# pcb_v1_mod.net
KiCad netlist of a schematic drawn in EAGLE
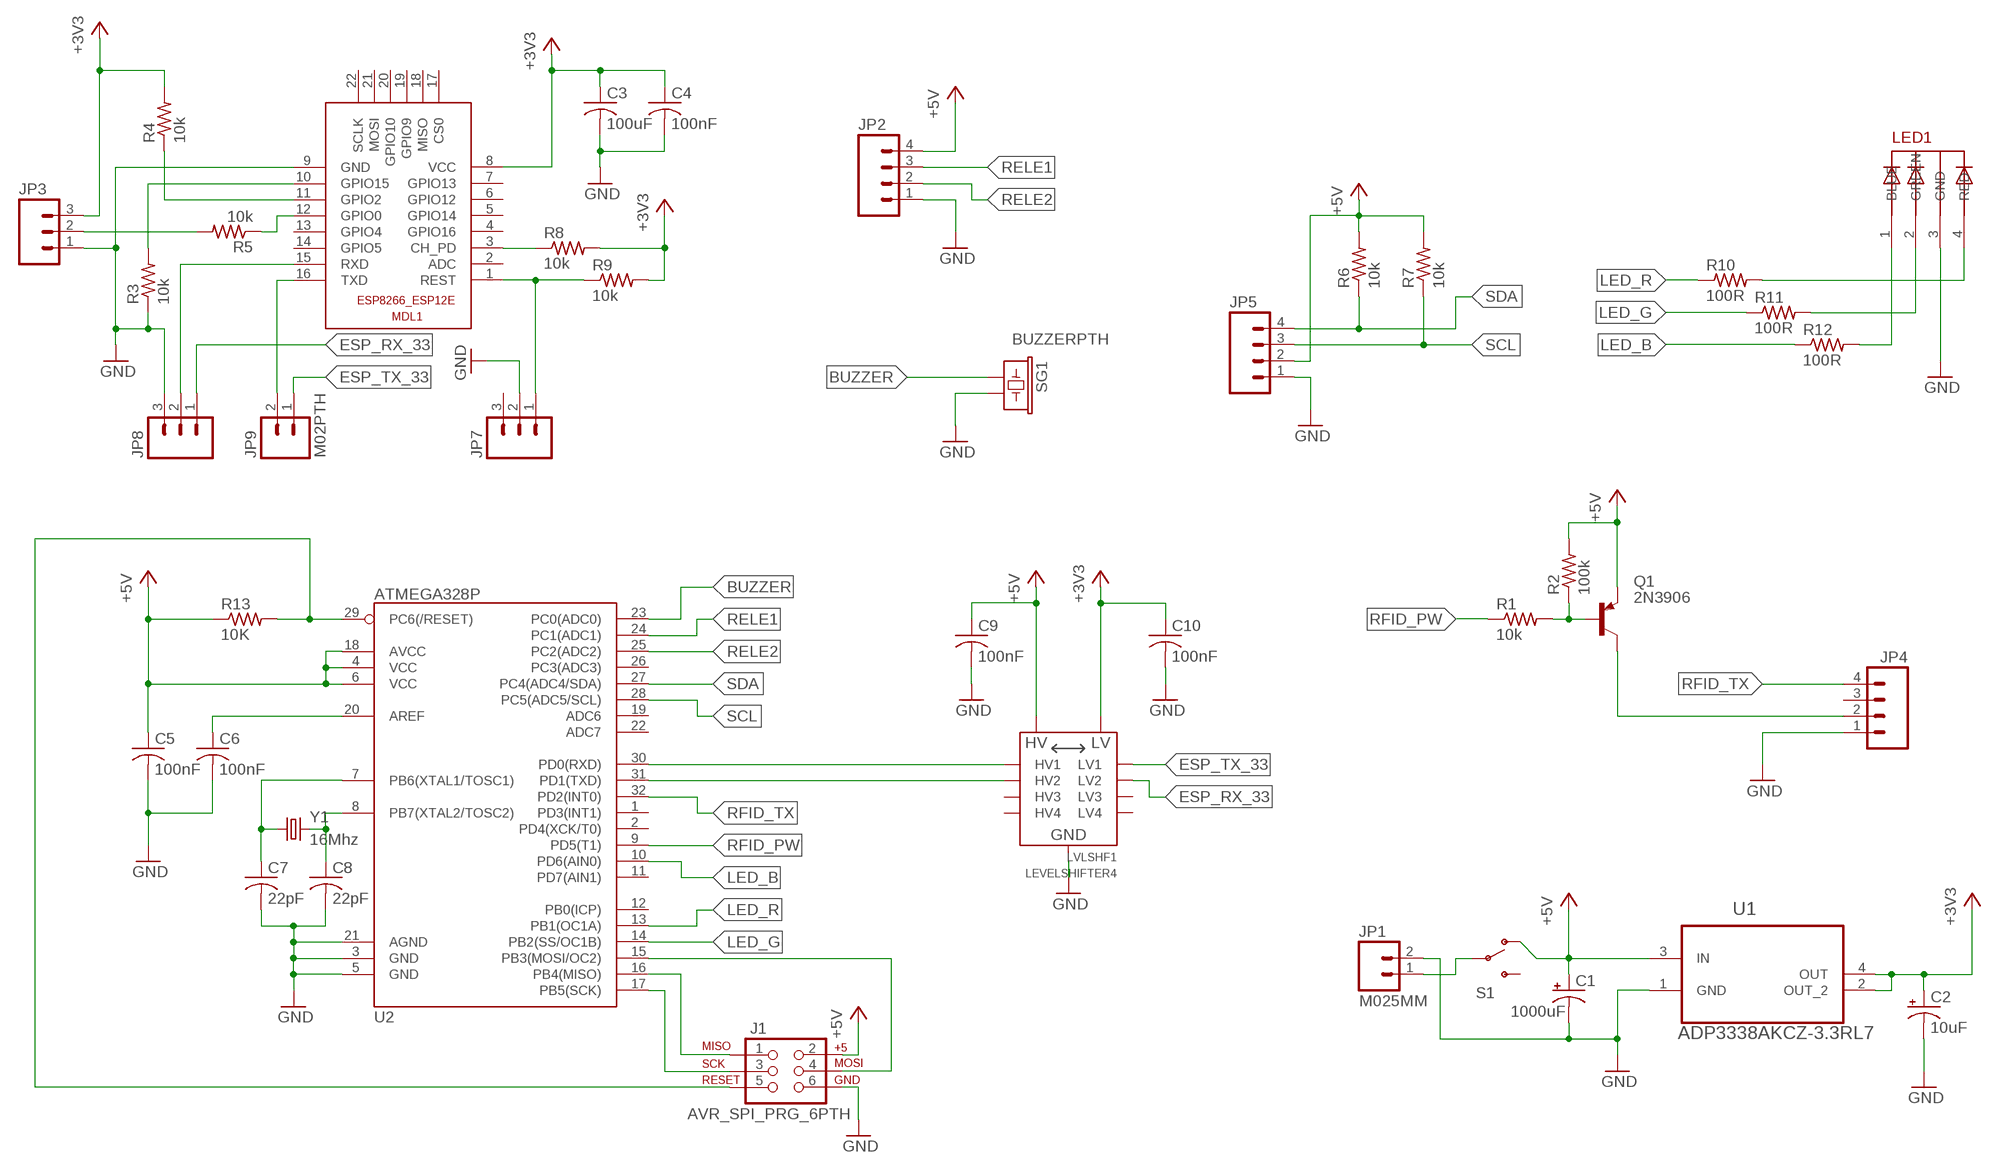
[diagram p0: schematic, sheet 1]

(export (version "E")
  (design (tool "Eeschema 10.0.6"))
  (components
    (comp (ref "C1")
      (value "1000uF")
      (footprint "eagle-import:E2,5-6")
      (libsource (lib "eagle-import") (part "CPOL-USE2.5-6"))
    )
    (comp (ref "C2")
      (value "10uF")
      (footprint "eagle-import:E2,5-6")
      (libsource (lib "eagle-import") (part "CPOL-USE2.5-6"))
    )
    (comp (ref "C3")
      (value "100uF")
      (footprint "eagle-import:C1206")
      (libsource (lib "eagle-import") (part "C-USC1206"))
    )
    (comp (ref "C4")
      (value "100nF")
      (footprint "eagle-import:C0805")
      (libsource (lib "eagle-import") (part "C-USC0805"))
    )
    (comp (ref "C5")
      (value "100nF")
      (footprint "eagle-import:C0805")
      (libsource (lib "eagle-import") (part "C-USC0805"))
    )
    (comp (ref "C6")
      (value "100nF")
      (footprint "eagle-import:C0805")
      (libsource (lib "eagle-import") (part "C-USC0805"))
    )
    (comp (ref "C7")
      (value "22pF")
      (footprint "eagle-import:C1206")
      (libsource (lib "eagle-import") (part "C-USC1206"))
    )
    (comp (ref "C8")
      (value "22pF")
      (footprint "eagle-import:C1206")
      (libsource (lib "eagle-import") (part "C-USC1206"))
    )
    (comp (ref "C9")
      (value "100nF")
      (footprint "eagle-import:C0805")
      (libsource (lib "eagle-import") (part "C-USC0805"))
    )
    (comp (ref "C10")
      (value "100nF")
      (footprint "eagle-import:C0805")
      (libsource (lib "eagle-import") (part "C-USC0805"))
    )
    (comp (ref "J1")
      (value "AVR_SPI_PRG_6PTH")
      (footprint "eagle-import:2X3")
      (libsource (lib "eagle-import") (part "AVR_SPI_PRG_6PTH"))
    )
    (comp (ref "JP1")
      (value "M025MM")
      (footprint "eagle-import:SCREWTERMINAL-5MM-2")
      (libsource (lib "eagle-import") (part "M025MM"))
    )
    (comp (ref "JP2")
      (value "M041X04_NO_SILK")
      (footprint "eagle-import:1X04_NO_SILK")
      (libsource (lib "eagle-import") (part "M041X04_NO_SILK"))
    )
    (comp (ref "JP3")
      (value "M03PTH")
      (footprint "eagle-import:1X03")
      (libsource (lib "eagle-import") (part "M03PTH"))
    )
    (comp (ref "JP4")
      (value "M041X04_NO_SILK")
      (footprint "eagle-import:1X04_NO_SILK")
      (libsource (lib "eagle-import") (part "M041X04_NO_SILK"))
    )
    (comp (ref "JP5")
      (value "M041X04_NO_SILK")
      (footprint "eagle-import:1X04_NO_SILK")
      (libsource (lib "eagle-import") (part "M041X04_NO_SILK"))
    )
    (comp (ref "JP7")
      (value "M03PTH")
      (footprint "eagle-import:1X03")
      (libsource (lib "eagle-import") (part "M03PTH"))
    )
    (comp (ref "JP8")
      (value "M03PTH")
      (footprint "eagle-import:1X03")
      (libsource (lib "eagle-import") (part "M03PTH"))
    )
    (comp (ref "JP9")
      (value "M02PTH")
      (footprint "eagle-import:1X02")
      (libsource (lib "eagle-import") (part "M02PTH"))
    )
    (comp (ref "LED1")
      (value "5MMRGBLED")
      (footprint "eagle-import:LED5MMRGB")
      (libsource (lib "eagle-import") (part "5MMRGBLED"))
    )
    (comp (ref "LVLSHF1")
      (value "LEVELSHIFTER4")
      (footprint "eagle-import:LEVELSHIFTER4")
      (libsource (lib "eagle-import") (part "LEVELSHIFTER4"))
    )
    (comp (ref "MDL1")
      (value "ESP8266-12EESP8266-ESP12E")
      (footprint "eagle-import:ESP8266-ESP12E")
      (libsource (lib "eagle-import") (part "ESP8266-12EESP8266-ESP12E"))
    )
    (comp (ref "Q1")
      (value "2N3906")
      (footprint "eagle-import:TO92")
      (libsource (lib "eagle-import") (part "2N3906"))
    )
    (comp (ref "R1")
      (value "10k")
      (footprint "eagle-import:R0805")
      (libsource (lib "eagle-import") (part "R-US_R0805"))
    )
    (comp (ref "R2")
      (value "100k")
      (footprint "eagle-import:R0805")
      (libsource (lib "eagle-import") (part "R-US_R0805"))
    )
    (comp (ref "R3")
      (value "10k")
      (footprint "eagle-import:R0805")
      (libsource (lib "eagle-import") (part "R-US_R0805"))
    )
    (comp (ref "R4")
      (value "10k")
      (footprint "eagle-import:R0805")
      (libsource (lib "eagle-import") (part "R-US_R0805"))
    )
    (comp (ref "R5")
      (value "10k")
      (footprint "eagle-import:R0805")
      (libsource (lib "eagle-import") (part "R-US_R0805"))
    )
    (comp (ref "R6")
      (value "10k")
      (footprint "eagle-import:R0805")
      (libsource (lib "eagle-import") (part "R-US_R0805"))
    )
    (comp (ref "R7")
      (value "10k")
      (footprint "eagle-import:R0805")
      (libsource (lib "eagle-import") (part "R-US_R0805"))
    )
    (comp (ref "R8")
      (value "10k")
      (footprint "eagle-import:R0805")
      (libsource (lib "eagle-import") (part "R-US_R0805"))
    )
    (comp (ref "R9")
      (value "10k")
      (footprint "eagle-import:R0805")
      (libsource (lib "eagle-import") (part "R-US_R0805"))
    )
    (comp (ref "R10")
      (value "100R")
      (footprint "eagle-import:R1206")
      (libsource (lib "eagle-import") (part "R-US_R1206"))
    )
    (comp (ref "R11")
      (value "100R")
      (footprint "eagle-import:R0805")
      (libsource (lib "eagle-import") (part "R-US_R0805"))
    )
    (comp (ref "R12")
      (value "100R")
      (footprint "eagle-import:R0805")
      (libsource (lib "eagle-import") (part "R-US_R0805"))
    )
    (comp (ref "R13")
      (value "10K")
      (footprint "eagle-import:R0805")
      (libsource (lib "eagle-import") (part "R-US_R0805"))
    )
    (comp (ref "S1")
      (value "SWITCH-SPDTPTH")
      (footprint "eagle-import:SWITCH-SPDT")
      (libsource (lib "eagle-import") (part "SWITCH-SPDTPTH"))
    )
    (comp (ref "SG1")
      (value "BUZZERPTH")
      (footprint "eagle-import:BUZZER-12MM")
      (libsource (lib "eagle-import") (part "BUZZERPTH"))
    )
    (comp (ref "U1")
      (value "ADP3338AKCZ-3.3RL7")
      (footprint "eagle-import:SOT230P700X180-4N")
      (libsource (lib "eagle-import") (part "ADP3338AKCZ-3.3RL7"))
    )
    (comp (ref "U2")
      (value "ATMEGA328P")
      (footprint "eagle-import:TQFP32-08")
      (libsource (lib "eagle-import") (part "ATMEGA328_SMT"))
    )
    (comp (ref "Y1")
      (value "16Mhz")
      (footprint "eagle-import:HC49US")
      (libsource (lib "eagle-import") (part "CRYSTALHC49US"))
    )
  )
  (nets
    (net (code "1") (name "+3V3") (class "Default")
      (node (ref "C10") (pin "1") (pinfunction "1_1") (pintype "passive"))
      (node (ref "C2") (pin "+") (pinfunction "+_+") (pintype "passive"))
      (node (ref "C3") (pin "1") (pinfunction "1_1") (pintype "passive"))
      (node (ref "C4") (pin "1") (pinfunction "1_1") (pintype "passive"))
      (node (ref "JP3") (pin "3") (pinfunction "3_3") (pintype "passive"))
      (node (ref "LVLSHF1") (pin "LV") (pinfunction "LV_LV") (pintype "power_in"))
      (node (ref "MDL1") (pin "8") (pinfunction "VCC_8") (pintype "bidirectional"))
      (node (ref "R4") (pin "2") (pinfunction "2_2") (pintype "passive"))
      (node (ref "R8") (pin "2") (pinfunction "2_2") (pintype "passive"))
      (node (ref "R9") (pin "2") (pinfunction "2_2") (pintype "passive"))
      (node (ref "U1") (pin "2") (pinfunction "OUT_2_2") (pintype "output"))
      (node (ref "U1") (pin "4") (pinfunction "OUT_4") (pintype "output"))
    )
    (net (code "2") (name "+5V") (class "Default")
      (node (ref "C1") (pin "+") (pinfunction "+_+") (pintype "passive"))
      (node (ref "C5") (pin "1") (pinfunction "1_1") (pintype "passive"))
      (node (ref "C9") (pin "1") (pinfunction "1_1") (pintype "passive"))
      (node (ref "J1") (pin "2") (pinfunction "2_2") (pintype "passive"))
      (node (ref "JP2") (pin "4") (pinfunction "4_4") (pintype "passive"))
      (node (ref "JP5") (pin "2") (pinfunction "2_2") (pintype "passive"))
      (node (ref "LVLSHF1") (pin "HV") (pinfunction "HV_HV") (pintype "power_in"))
      (node (ref "Q1") (pin "3") (pinfunction "E_3") (pintype "passive"))
      (node (ref "R13") (pin "1") (pinfunction "1_1") (pintype "passive"))
      (node (ref "R2") (pin "2") (pinfunction "2_2") (pintype "passive"))
      (node (ref "R6") (pin "2") (pinfunction "2_2") (pintype "passive"))
      (node (ref "R7") (pin "2") (pinfunction "2_2") (pintype "passive"))
      (node (ref "S1") (pin "1") (pinfunction "O_1") (pintype "passive"))
      (node (ref "U1") (pin "3") (pinfunction "IN_3") (pintype "input"))
      (node (ref "U2") (pin "18") (pinfunction "AVCC_18") (pintype "bidirectional"))
      (node (ref "U2") (pin "4") (pinfunction "VCC_4") (pintype "bidirectional"))
      (node (ref "U2") (pin "6") (pinfunction "VCC_6") (pintype "bidirectional"))
    )
    (net (code "3") (name "BUZZER") (class "Default")
      (node (ref "SG1") (pin "+") (pinfunction "1_+") (pintype "passive"))
      (node (ref "U2") (pin "23") (pinfunction "PC0(ADC0)_23") (pintype "bidirectional"))
    )
    (net (code "4") (name "ESP_RX_33") (class "Default")
      (node (ref "JP8") (pin "1") (pinfunction "1_1") (pintype "passive"))
      (node (ref "LVLSHF1") (pin "LV2") (pinfunction "LV2_LV2") (pintype "bidirectional"))
    )
    (net (code "5") (name "ESP_TX_33") (class "Default")
      (node (ref "JP9") (pin "1") (pinfunction "1_1") (pintype "passive"))
      (node (ref "LVLSHF1") (pin "LV1") (pinfunction "LV1_LV1") (pintype "bidirectional"))
    )
    (net (code "6") (name "GND") (class "Default")
      (node (ref "C1") (pin "-") (pinfunction "-_-") (pintype "passive"))
      (node (ref "C10") (pin "2") (pinfunction "2_2") (pintype "passive"))
      (node (ref "C2") (pin "-") (pinfunction "-_-") (pintype "passive"))
      (node (ref "C3") (pin "2") (pinfunction "2_2") (pintype "passive"))
      (node (ref "C4") (pin "2") (pinfunction "2_2") (pintype "passive"))
      (node (ref "C5") (pin "2") (pinfunction "2_2") (pintype "passive"))
      (node (ref "C6") (pin "2") (pinfunction "2_2") (pintype "passive"))
      (node (ref "C7") (pin "2") (pinfunction "2_2") (pintype "passive"))
      (node (ref "C8") (pin "2") (pinfunction "2_2") (pintype "passive"))
      (node (ref "C9") (pin "2") (pinfunction "2_2") (pintype "passive"))
      (node (ref "J1") (pin "6") (pinfunction "6_6") (pintype "passive"))
      (node (ref "JP1") (pin "2") (pinfunction "2_2") (pintype "passive"))
      (node (ref "JP2") (pin "1") (pinfunction "1_1") (pintype "passive"))
      (node (ref "JP3") (pin "1") (pinfunction "1_1") (pintype "passive"))
      (node (ref "JP4") (pin "1") (pinfunction "1_1") (pintype "passive"))
      (node (ref "JP5") (pin "1") (pinfunction "1_1") (pintype "passive"))
      (node (ref "JP7") (pin "2") (pinfunction "2_2") (pintype "passive"))
      (node (ref "JP8") (pin "3") (pinfunction "3_3") (pintype "passive"))
      (node (ref "LED1") (pin "3") (pinfunction "GND_3") (pintype "bidirectional"))
      (node (ref "LVLSHF1") (pin "GND") (pinfunction "GND_GND") (pintype "bidirectional"))
      (node (ref "LVLSHF1") (pin "GND1") (pinfunction "GND_GND1") (pintype "bidirectional"))
      (node (ref "MDL1") (pin "9") (pinfunction "GND_9") (pintype "bidirectional"))
      (node (ref "R3") (pin "1") (pinfunction "1_1") (pintype "passive"))
      (node (ref "SG1") (pin "-") (pinfunction "2_-") (pintype "passive"))
      (node (ref "U1") (pin "1") (pinfunction "GND_1") (pintype "passive"))
      (node (ref "U2") (pin "21") (pinfunction "AGND_21") (pintype "bidirectional"))
      (node (ref "U2") (pin "3") (pinfunction "GND_3") (pintype "bidirectional"))
      (node (ref "U2") (pin "5") (pinfunction "GND_5") (pintype "bidirectional"))
    )
    (net (code "7") (name "LED_B") (class "Default")
      (node (ref "R12") (pin "1") (pinfunction "1_1") (pintype "passive"))
      (node (ref "U2") (pin "10") (pinfunction "PD6(AIN0)_10") (pintype "bidirectional"))
    )
    (net (code "8") (name "LED_G") (class "Default")
      (node (ref "R11") (pin "1") (pinfunction "1_1") (pintype "passive"))
      (node (ref "U2") (pin "14") (pinfunction "PB2(SS/OC1B)_14") (pintype "bidirectional"))
    )
    (net (code "9") (name "LED_R") (class "Default")
      (node (ref "R10") (pin "1") (pinfunction "1_1") (pintype "passive"))
      (node (ref "U2") (pin "13") (pinfunction "PB1(OC1A)_13") (pintype "bidirectional"))
    )
    (net (code "10") (name "Net-(JP3-Pad2)") (class "Default")
      (node (ref "JP3") (pin "2") (pinfunction "2_2") (pintype "passive"))
      (node (ref "R5") (pin "2") (pinfunction "2_2") (pintype "passive"))
    )
    (net (code "11") (name "Net-(LED1-BLUE)") (class "Default")
      (node (ref "LED1") (pin "1") (pinfunction "BLUE_1") (pintype "bidirectional"))
      (node (ref "R12") (pin "2") (pinfunction "2_2") (pintype "passive"))
    )
    (net (code "12") (name "Net-(LED1-GREEN)") (class "Default")
      (node (ref "LED1") (pin "2") (pinfunction "GREEN_2") (pintype "bidirectional"))
      (node (ref "R11") (pin "2") (pinfunction "2_2") (pintype "passive"))
    )
    (net (code "13") (name "Net-(LED1-RED)") (class "Default")
      (node (ref "LED1") (pin "4") (pinfunction "RED_4") (pintype "bidirectional"))
      (node (ref "R10") (pin "2") (pinfunction "2_2") (pintype "passive"))
    )
    (net (code "14") (name "Net-(MDL1-CH_PD)") (class "Default")
      (node (ref "MDL1") (pin "3") (pinfunction "CH_PD_3") (pintype "bidirectional"))
      (node (ref "R8") (pin "1") (pinfunction "1_1") (pintype "passive"))
    )
    (net (code "15") (name "Net-(MDL1-GPIO0)") (class "Default")
      (node (ref "MDL1") (pin "12") (pinfunction "GPIO0_12") (pintype "bidirectional"))
      (node (ref "R5") (pin "1") (pinfunction "1_1") (pintype "passive"))
    )
    (net (code "16") (name "Net-(MDL1-GPIO2)") (class "Default")
      (node (ref "MDL1") (pin "11") (pinfunction "GPIO2_11") (pintype "bidirectional"))
      (node (ref "R4") (pin "1") (pinfunction "1_1") (pintype "passive"))
    )
    (net (code "17") (name "Net-(MDL1-GPIO15)") (class "Default")
      (node (ref "MDL1") (pin "10") (pinfunction "GPIO15_10") (pintype "bidirectional"))
      (node (ref "R3") (pin "2") (pinfunction "2_2") (pintype "passive"))
    )
    (net (code "18") (name "Net-(MDL1-REST)") (class "Default")
      (node (ref "JP7") (pin "1") (pinfunction "1_1") (pintype "passive"))
      (node (ref "MDL1") (pin "1") (pinfunction "REST_1") (pintype "bidirectional"))
      (node (ref "R9") (pin "1") (pinfunction "1_1") (pintype "passive"))
    )
    (net (code "19") (name "Net-(MDL1-RXD)") (class "Default")
      (node (ref "JP8") (pin "2") (pinfunction "2_2") (pintype "passive"))
      (node (ref "MDL1") (pin "15") (pinfunction "RXD_15") (pintype "bidirectional"))
    )
    (net (code "20") (name "Net-(MDL1-TXD)") (class "Default")
      (node (ref "JP9") (pin "2") (pinfunction "2_2") (pintype "passive"))
      (node (ref "MDL1") (pin "16") (pinfunction "TXD_16") (pintype "bidirectional"))
    )
    (net (code "21") (name "Net-(Q1-B)") (class "Default")
      (node (ref "Q1") (pin "2") (pinfunction "B_2") (pintype "passive"))
      (node (ref "R1") (pin "2") (pinfunction "2_2") (pintype "passive"))
      (node (ref "R2") (pin "1") (pinfunction "1_1") (pintype "passive"))
    )
    (net (code "22") (name "Net-(Q1-C)") (class "Default")
      (node (ref "JP4") (pin "2") (pinfunction "2_2") (pintype "passive"))
      (node (ref "Q1") (pin "1") (pinfunction "C_1") (pintype "passive"))
    )
    (net (code "23") (name "Net-(S1-P)") (class "Default")
      (node (ref "JP1") (pin "1") (pinfunction "1_1") (pintype "passive"))
      (node (ref "S1") (pin "2") (pinfunction "P_2") (pintype "passive"))
    )
    (net (code "24") (name "Net-(U2-AREF)") (class "Default")
      (node (ref "C6") (pin "1") (pinfunction "1_1") (pintype "passive"))
      (node (ref "U2") (pin "20") (pinfunction "AREF_20") (pintype "bidirectional"))
    )
    (net (code "25") (name "Net-(U2-PB3(MOSI{slash}OC2))") (class "Default")
      (node (ref "J1") (pin "4") (pinfunction "4_4") (pintype "passive"))
      (node (ref "U2") (pin "15") (pinfunction "PB3(MOSI/OC2)_15") (pintype "bidirectional"))
    )
    (net (code "26") (name "Net-(U2-PB4(MISO))") (class "Default")
      (node (ref "J1") (pin "1") (pinfunction "1_1") (pintype "passive"))
      (node (ref "U2") (pin "16") (pinfunction "PB4(MISO)_16") (pintype "bidirectional"))
    )
    (net (code "27") (name "Net-(U2-PB5(SCK))") (class "Default")
      (node (ref "J1") (pin "3") (pinfunction "3_3") (pintype "passive"))
      (node (ref "U2") (pin "17") (pinfunction "PB5(SCK)_17") (pintype "bidirectional"))
    )
    (net (code "28") (name "Net-(U2-PB6(XTAL1{slash}TOSC1))") (class "Default")
      (node (ref "C7") (pin "1") (pinfunction "1_1") (pintype "passive"))
      (node (ref "U2") (pin "7") (pinfunction "PB6(XTAL1/TOSC1)_7") (pintype "bidirectional"))
      (node (ref "Y1") (pin "1") (pinfunction "1_1") (pintype "passive"))
    )
    (net (code "29") (name "Net-(U2-PB7(XTAL2{slash}TOSC2))") (class "Default")
      (node (ref "C8") (pin "1") (pinfunction "1_1") (pintype "passive"))
      (node (ref "U2") (pin "8") (pinfunction "PB7(XTAL2/TOSC2)_8") (pintype "bidirectional"))
      (node (ref "Y1") (pin "2") (pinfunction "2_2") (pintype "passive"))
    )
    (net (code "30") (name "Net-(U2-PC6({slash}RESET))") (class "Default")
      (node (ref "J1") (pin "5") (pinfunction "5_5") (pintype "passive"))
      (node (ref "R13") (pin "2") (pinfunction "2_2") (pintype "passive"))
      (node (ref "U2") (pin "29") (pinfunction "PC6(/RESET)_29") (pintype "bidirectional"))
    )
    (net (code "31") (name "Net-(U2-PD0(RXD))") (class "Default")
      (node (ref "LVLSHF1") (pin "HV1") (pinfunction "HV1_HV1") (pintype "bidirectional"))
      (node (ref "U2") (pin "30") (pinfunction "PD0(RXD)_30") (pintype "bidirectional"))
    )
    (net (code "32") (name "Net-(U2-PD1(TXD))") (class "Default")
      (node (ref "LVLSHF1") (pin "HV2") (pinfunction "HV2_HV2") (pintype "bidirectional"))
      (node (ref "U2") (pin "31") (pinfunction "PD1(TXD)_31") (pintype "bidirectional"))
    )
    (net (code "33") (name "RELE1") (class "Default")
      (node (ref "JP2") (pin "3") (pinfunction "3_3") (pintype "passive"))
      (node (ref "U2") (pin "24") (pinfunction "PC1(ADC1)_24") (pintype "bidirectional"))
    )
    (net (code "34") (name "RELE2") (class "Default")
      (node (ref "JP2") (pin "2") (pinfunction "2_2") (pintype "passive"))
      (node (ref "U2") (pin "25") (pinfunction "PC2(ADC2)_25") (pintype "bidirectional"))
    )
    (net (code "35") (name "RFID_PW") (class "Default")
      (node (ref "R1") (pin "1") (pinfunction "1_1") (pintype "passive"))
      (node (ref "U2") (pin "9") (pinfunction "PD5(T1)_9") (pintype "bidirectional"))
    )
    (net (code "36") (name "RFID_TX") (class "Default")
      (node (ref "JP4") (pin "4") (pinfunction "4_4") (pintype "passive"))
      (node (ref "U2") (pin "32") (pinfunction "PD2(INT0)_32") (pintype "bidirectional"))
    )
    (net (code "37") (name "SCL") (class "Default")
      (node (ref "JP5") (pin "3") (pinfunction "3_3") (pintype "passive"))
      (node (ref "R7") (pin "1") (pinfunction "1_1") (pintype "passive"))
      (node (ref "U2") (pin "28") (pinfunction "PC5(ADC5/SCL)_28") (pintype "bidirectional"))
    )
    (net (code "38") (name "SDA") (class "Default")
      (node (ref "JP5") (pin "4") (pinfunction "4_4") (pintype "passive"))
      (node (ref "R6") (pin "1") (pinfunction "1_1") (pintype "passive"))
      (node (ref "U2") (pin "27") (pinfunction "PC4(ADC4/SDA)_27") (pintype "bidirectional"))
    )
    (net (code "39") (name "unconnected-(JP4-Pad3)") (class "Default")
      (node (ref "JP4") (pin "3") (pinfunction "3_3") (pintype "passive"))
    )
    (net (code "40") (name "unconnected-(JP7-Pad3)") (class "Default")
      (node (ref "JP7") (pin "3") (pinfunction "3_3") (pintype "passive"))
    )
    (net (code "41") (name "unconnected-(LVLSHF1-PadHV3)") (class "Default")
      (node (ref "LVLSHF1") (pin "HV3") (pinfunction "HV3_HV3") (pintype "input"))
    )
    (net (code "42") (name "unconnected-(LVLSHF1-PadHV4)") (class "Default")
      (node (ref "LVLSHF1") (pin "HV4") (pinfunction "HV4_HV4") (pintype "input"))
    )
    (net (code "43") (name "unconnected-(LVLSHF1-PadLV3)") (class "Default")
      (node (ref "LVLSHF1") (pin "LV3") (pinfunction "LV3_LV3") (pintype "output"))
    )
    (net (code "44") (name "unconnected-(LVLSHF1-PadLV4)") (class "Default")
      (node (ref "LVLSHF1") (pin "LV4") (pinfunction "LV4_LV4") (pintype "output"))
    )
    (net (code "45") (name "unconnected-(MDL1-ADC-Pad2)") (class "Default")
      (node (ref "MDL1") (pin "2") (pinfunction "ADC_2") (pintype "bidirectional"))
    )
    (net (code "46") (name "unconnected-(MDL1-CS0-Pad17)") (class "Default")
      (node (ref "MDL1") (pin "17") (pinfunction "CS0_17") (pintype "bidirectional"))
    )
    (net (code "47") (name "unconnected-(MDL1-GPIO4-Pad13)") (class "Default")
      (node (ref "MDL1") (pin "13") (pinfunction "GPIO4_13") (pintype "bidirectional"))
    )
    (net (code "48") (name "unconnected-(MDL1-GPIO5-Pad14)") (class "Default")
      (node (ref "MDL1") (pin "14") (pinfunction "GPIO5_14") (pintype "bidirectional"))
    )
    (net (code "49") (name "unconnected-(MDL1-GPIO9-Pad19)") (class "Default")
      (node (ref "MDL1") (pin "19") (pinfunction "GPIO9_19") (pintype "bidirectional"))
    )
    (net (code "50") (name "unconnected-(MDL1-GPIO10-Pad20)") (class "Default")
      (node (ref "MDL1") (pin "20") (pinfunction "GPIO10_20") (pintype "bidirectional"))
    )
    (net (code "51") (name "unconnected-(MDL1-GPIO12-Pad6)") (class "Default")
      (node (ref "MDL1") (pin "6") (pinfunction "GPIO12_6") (pintype "bidirectional"))
    )
    (net (code "52") (name "unconnected-(MDL1-GPIO13-Pad7)") (class "Default")
      (node (ref "MDL1") (pin "7") (pinfunction "GPIO13_7") (pintype "bidirectional"))
    )
    (net (code "53") (name "unconnected-(MDL1-GPIO14-Pad5)") (class "Default")
      (node (ref "MDL1") (pin "5") (pinfunction "GPIO14_5") (pintype "bidirectional"))
    )
    (net (code "54") (name "unconnected-(MDL1-GPIO16-Pad4)") (class "Default")
      (node (ref "MDL1") (pin "4") (pinfunction "GPIO16_4") (pintype "bidirectional"))
    )
    (net (code "55") (name "unconnected-(MDL1-MISO-Pad18)") (class "Default")
      (node (ref "MDL1") (pin "18") (pinfunction "MISO_18") (pintype "bidirectional"))
    )
    (net (code "56") (name "unconnected-(MDL1-MOSI-Pad21)") (class "Default")
      (node (ref "MDL1") (pin "21") (pinfunction "MOSI_21") (pintype "bidirectional"))
    )
    (net (code "57") (name "unconnected-(MDL1-SCLK-Pad22)") (class "Default")
      (node (ref "MDL1") (pin "22") (pinfunction "SCLK_22") (pintype "bidirectional"))
    )
    (net (code "58") (name "unconnected-(S1-S-Pad3)") (class "Default")
      (node (ref "S1") (pin "3") (pinfunction "S_3") (pintype "passive"))
    )
    (net (code "59") (name "unconnected-(U2-ADC6-Pad19)") (class "Default")
      (node (ref "U2") (pin "19") (pinfunction "ADC6_19") (pintype "bidirectional"))
    )
    (net (code "60") (name "unconnected-(U2-ADC7-Pad22)") (class "Default")
      (node (ref "U2") (pin "22") (pinfunction "ADC7_22") (pintype "bidirectional"))
    )
    (net (code "61") (name "unconnected-(U2-PB0(ICP)-Pad12)") (class "Default")
      (node (ref "U2") (pin "12") (pinfunction "PB0(ICP)_12") (pintype "bidirectional"))
    )
    (net (code "62") (name "unconnected-(U2-PC3(ADC3)-Pad26)") (class "Default")
      (node (ref "U2") (pin "26") (pinfunction "PC3(ADC3)_26") (pintype "bidirectional"))
    )
    (net (code "63") (name "unconnected-(U2-PD3(INT1)-Pad1)") (class "Default")
      (node (ref "U2") (pin "1") (pinfunction "PD3(INT1)_1") (pintype "bidirectional"))
    )
    (net (code "64") (name "unconnected-(U2-PD4(XCK{slash}T0)-Pad2)") (class "Default")
      (node (ref "U2") (pin "2") (pinfunction "PD4(XCK/T0)_2") (pintype "bidirectional"))
    )
    (net (code "65") (name "unconnected-(U2-PD7(AIN1)-Pad11)") (class "Default")
      (node (ref "U2") (pin "11") (pinfunction "PD7(AIN1)_11") (pintype "bidirectional"))
    )
  )
)
